# battery_monitor_6803-2_Rev3.net
KiCad netlist of a schematic drawn in EAGLE
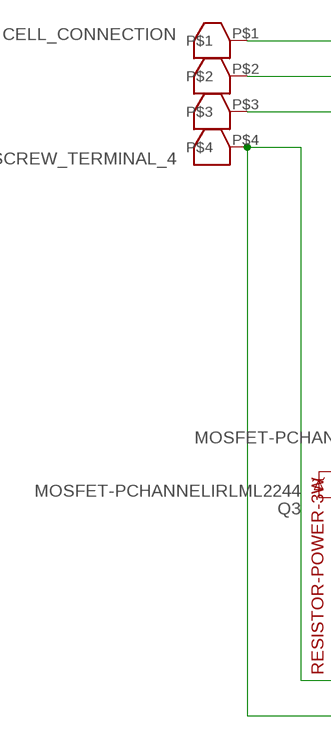
[diagram p0: schematic, sheet 1, part 1 of 2]
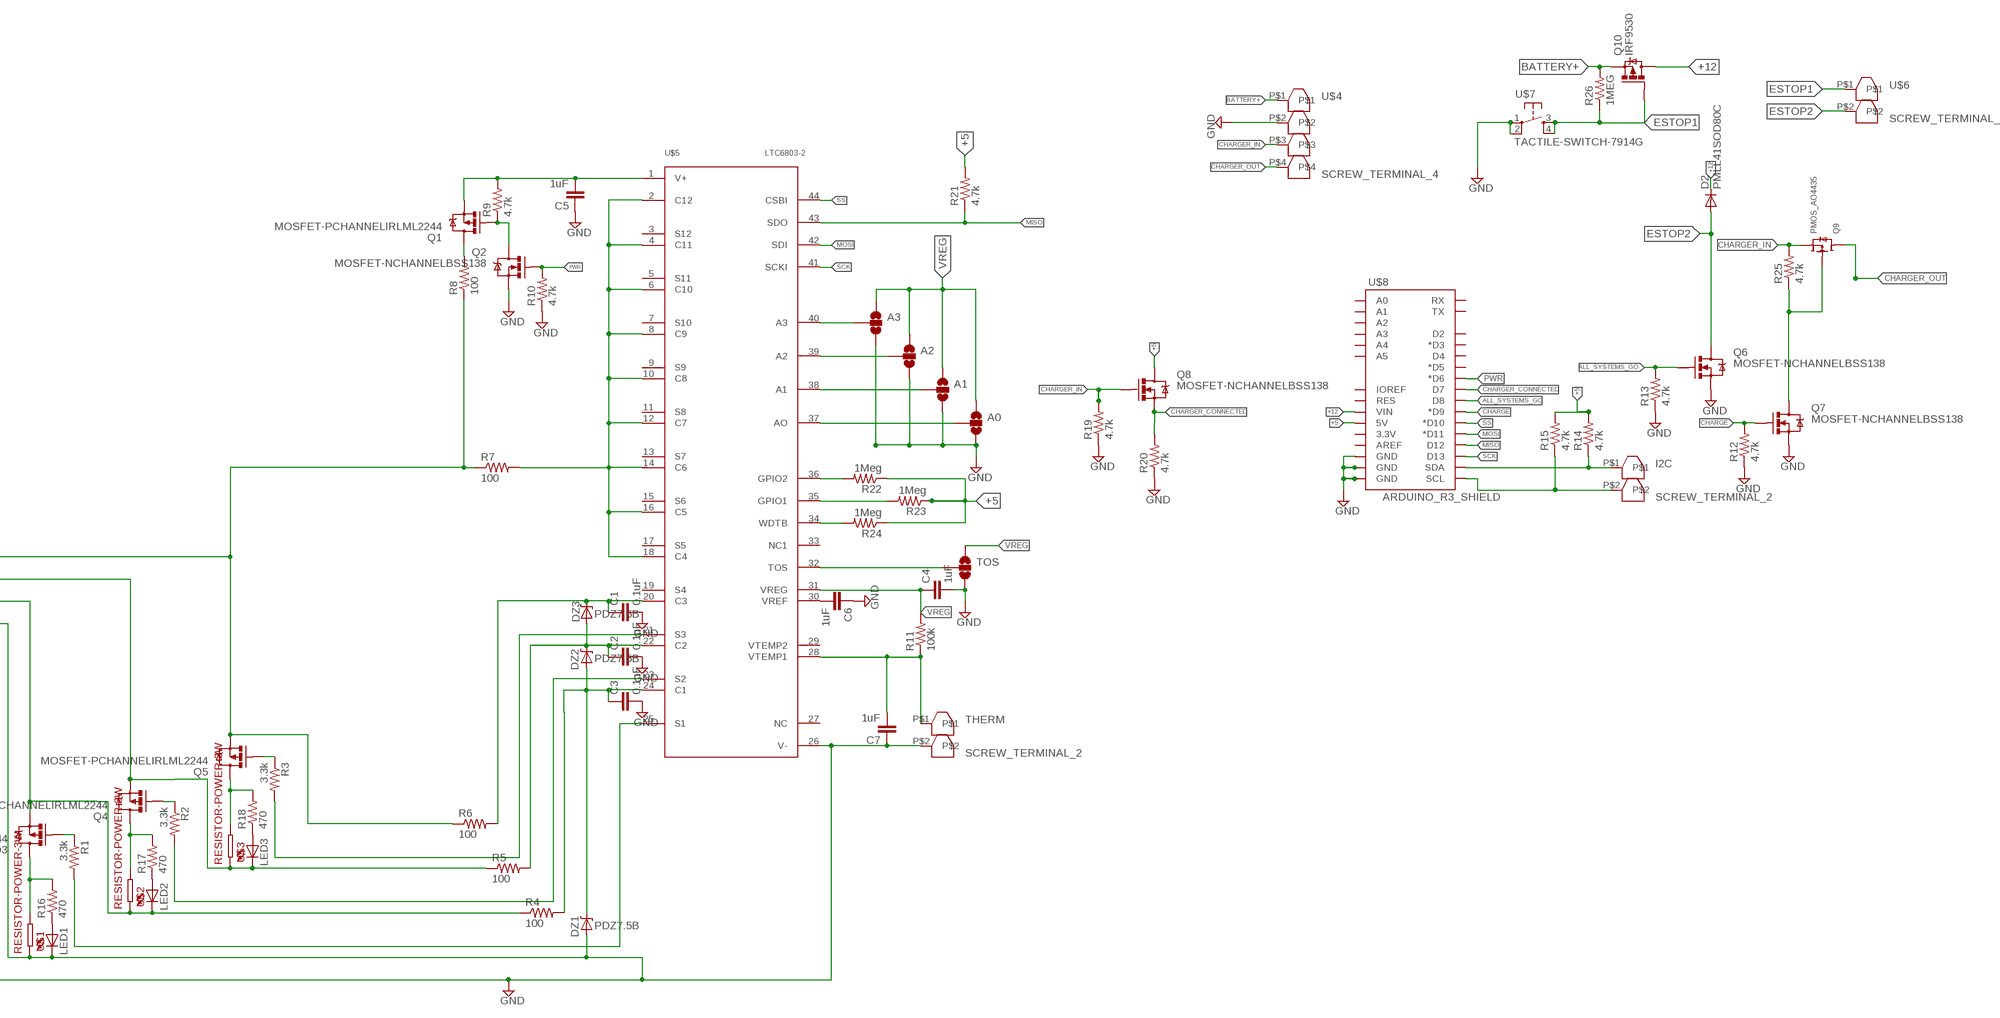
[diagram p1: schematic, sheet 1, part 2 of 2]

(export (version "E")
  (design (tool "Eeschema 10.0.6"))
  (components
    (comp (ref "A0")
      (value "SOLDERJUMPER_2WAYS")
      (footprint "eagle-import:SJ_3")
      (libsource (lib "eagle-import") (part "SOLDERJUMPER_2WAYS"))
    )
    (comp (ref "A1")
      (value "SOLDERJUMPER_2WAYS")
      (footprint "eagle-import:SJ_3")
      (libsource (lib "eagle-import") (part "SOLDERJUMPER_2WAYS"))
    )
    (comp (ref "A2")
      (value "SOLDERJUMPER_2WAYS")
      (footprint "eagle-import:SJ_3")
      (libsource (lib "eagle-import") (part "SOLDERJUMPER_2WAYS"))
    )
    (comp (ref "A3")
      (value "SOLDERJUMPER_2WAYS")
      (footprint "eagle-import:SJ_3")
      (libsource (lib "eagle-import") (part "SOLDERJUMPER_2WAYS"))
    )
    (comp (ref "C1")
      (value "0.1uF")
      (footprint "eagle-import:0603-CAP")
      (fields (field (name "MF") "AVX CORPORATION") (field (name "MPN") "0603YG104ZAT2A"))
      (libsource (lib "eagle-import") (part "0.1UF-100V-10%(0603)"))
    )
    (comp (ref "C2")
      (value "0.1uF")
      (footprint "eagle-import:0603-CAP")
      (fields (field (name "MF") "AVX CORPORATION") (field (name "MPN") "0603YG104ZAT2A"))
      (libsource (lib "eagle-import") (part "0.1UF-100V-10%(0603)"))
    )
    (comp (ref "C3")
      (value "0.1uF")
      (footprint "eagle-import:0603-CAP")
      (fields (field (name "MF") "AVX CORPORATION") (field (name "MPN") "0603YG104ZAT2A"))
      (libsource (lib "eagle-import") (part "0.1UF-100V-10%(0603)"))
    )
    (comp (ref "C4")
      (value "1uF")
      (footprint "eagle-import:0603-CAP")
      (fields (field (name "MPN") "C0603X5R0J105M030BC") (field (name "PROD_ID") "CAP-08390"))
      (libsource (lib "eagle-import") (part "0.1UF-100V-10%(0603)"))
    )
    (comp (ref "C5")
      (value "1uF")
      (footprint "eagle-import:0603-CAP")
      (fields (field (name "MPN") "C0603X5R0J105M030BC") (field (name "PROD_ID") "CAP-08390"))
      (libsource (lib "eagle-import") (part "0.1UF-100V-10%(0603)"))
    )
    (comp (ref "C6")
      (value "1uF")
      (footprint "eagle-import:0603-CAP")
      (fields (field (name "MPN") "C0603X5R0J105M030BC") (field (name "PROD_ID") "CAP-08390"))
      (libsource (lib "eagle-import") (part "0.1UF-100V-10%(0603)"))
    )
    (comp (ref "C7")
      (value "1uF")
      (footprint "eagle-import:0603-CAP")
      (fields (field (name "MPN") "C0603X5R0J105M030BC") (field (name "PROD_ID") "CAP-08390"))
      (libsource (lib "eagle-import") (part "0.1UF-100V-10%(0603)"))
    )
    (comp (ref "CELL_CONNECTION")
      (value "SCREW_TERMINAL_4")
      (footprint "eagle-import:SCREW_TERMINAL_4")
      (fields (field (name "MF") "TYCO ELECTRONICS") (field (name "MPN") "282834-4"))
      (libsource (lib "eagle-import") (part "SCREW_TERMINAL_4"))
    )
    (comp (ref "D2")
      (value "PMLL41SOD80C")
      (footprint "eagle-import:SOD80C")
      (fields (field (name "MF") "FAIRCHILD SEMICONDUCTOR") (field (name "MPN") "FDLL4148"))
      (libsource (lib "eagle-import") (part "PMLL41SOD80C"))
    )
    (comp (ref "DZ1")
      (value "PDZ7.5B")
      (footprint "eagle-import:SOD-323")
      (fields (field (name "MPN") "PDZ7.5B,115"))
      (libsource (lib "eagle-import") (part "DIODE-ZENER-BZT52"))
    )
    (comp (ref "DZ2")
      (value "PDZ7.5B")
      (footprint "eagle-import:SOD-323")
      (fields (field (name "MPN") "PDZ7.5B,115"))
      (libsource (lib "eagle-import") (part "DIODE-ZENER-BZT52"))
    )
    (comp (ref "DZ3")
      (value "PDZ7.5B")
      (footprint "eagle-import:SOD-323")
      (fields (field (name "MPN") "PDZ7.5B,115"))
      (libsource (lib "eagle-import") (part "DIODE-ZENER-BZT52"))
    )
    (comp (ref "I2C")
      (value "SCREW_TERMINAL_2")
      (footprint "eagle-import:SCREW_TERMINAL_2")
      (fields (field (name "MF") "TYCO ELECTRONICS") (field (name "MPN") "282834-2"))
      (libsource (lib "eagle-import") (part "isaac1_SCREW_TERMINAL_2"))
    )
    (comp (ref "LED1")
      (value "LED0603")
      (footprint "eagle-import:LED-0603")
      (fields (field (name "MPN") "150060RS75000"))
      (libsource (lib "eagle-import") (part "LED0603"))
    )
    (comp (ref "LED2")
      (value "LED0603")
      (footprint "eagle-import:LED-0603")
      (fields (field (name "MPN") "150060RS75000"))
      (libsource (lib "eagle-import") (part "LED0603"))
    )
    (comp (ref "LED3")
      (value "LED0603")
      (footprint "eagle-import:LED-0603")
      (fields (field (name "MPN") "150060RS75000"))
      (libsource (lib "eagle-import") (part "LED0603"))
    )
    (comp (ref "Q1")
      (value "MOSFET-PCHANNELIRLML2244")
      (footprint "eagle-import:SOT23-3")
      (fields (field (name "MPN") "SI2369DS-T1-GE3"))
      (libsource (lib "eagle-import") (part "MOSFET-PCHANNELIRLML2244"))
    )
    (comp (ref "Q2")
      (value "MOSFET-NCHANNELBSS138")
      (footprint "eagle-import:SOT23")
      (fields (field (name "MPN") "IRLML0030TRPBF"))
      (libsource (lib "eagle-import") (part "MOSFET-NCHANNELBSS138"))
    )
    (comp (ref "Q3")
      (value "MOSFET-PCHANNELIRLML2244")
      (footprint "eagle-import:SOT23-3")
      (fields (field (name "MPN") "SI2369DS-T1-GE3"))
      (libsource (lib "eagle-import") (part "MOSFET-PCHANNELIRLML2244"))
    )
    (comp (ref "Q4")
      (value "MOSFET-PCHANNELIRLML2244")
      (footprint "eagle-import:SOT23-3")
      (fields (field (name "MPN") "SI2369DS-T1-GE3"))
      (libsource (lib "eagle-import") (part "MOSFET-PCHANNELIRLML2244"))
    )
    (comp (ref "Q5")
      (value "MOSFET-PCHANNELIRLML2244")
      (footprint "eagle-import:SOT23-3")
      (fields (field (name "MPN") "SI2369DS-T1-GE3"))
      (libsource (lib "eagle-import") (part "MOSFET-PCHANNELIRLML2244"))
    )
    (comp (ref "Q6")
      (value "MOSFET-NCHANNELBSS138")
      (footprint "eagle-import:SOT23")
      (fields (field (name "MPN") "IRLML0030TRPBF"))
      (libsource (lib "eagle-import") (part "MOSFET-NCHANNELBSS138"))
    )
    (comp (ref "Q7")
      (value "MOSFET-NCHANNELBSS138")
      (footprint "eagle-import:SOT23")
      (fields (field (name "MPN") "IRLML0030TRPBF"))
      (libsource (lib "eagle-import") (part "MOSFET-NCHANNELBSS138"))
    )
    (comp (ref "Q8")
      (value "MOSFET-NCHANNELBSS138")
      (footprint "eagle-import:SOT23")
      (fields (field (name "MPN") "IRLML0030TRPBF") (field (name "PROD_ID") "TRANS-00830"))
      (libsource (lib "eagle-import") (part "MOSFET-NCHANNELBSS138"))
    )
    (comp (ref "Q9")
      (value "PMOS_AO4435")
      (footprint "eagle-import:SOIC8")
      (fields (field (name "MPN") "SI9407BDY-T1-GE3"))
      (libsource (lib "eagle-import") (part "PMOS_AO4435"))
    )
    (comp (ref "Q10")
      (value "IRF9530")
      (footprint "eagle-import:TO220BV")
      (fields (field (name "MPN") "NTE2383"))
      (libsource (lib "eagle-import") (part "IRF9530"))
    )
    (comp (ref "R1")
      (value "3.3k")
      (footprint "eagle-import:0603-RES")
      (fields (field (name "MF") "VISHAY/DALE") (field (name "MPN") "CRCW06033K00FKEA"))
      (libsource (lib "eagle-import") (part "3.3KOHM1/10W1%(0603)"))
    )
    (comp (ref "R2")
      (value "3.3k")
      (footprint "eagle-import:0603-RES")
      (fields (field (name "MF") "VISHAY/DALE") (field (name "MPN") "CRCW06033K00FKEA"))
      (libsource (lib "eagle-import") (part "3.3KOHM1/10W1%(0603)"))
    )
    (comp (ref "R3")
      (value "3.3k")
      (footprint "eagle-import:0603-RES")
      (fields (field (name "MF") "VISHAY/DALE") (field (name "MPN") "CRCW06033K00FKEA"))
      (libsource (lib "eagle-import") (part "3.3KOHM1/10W1%(0603)"))
    )
    (comp (ref "R4")
      (value "100")
      (footprint "eagle-import:0603-RES")
      (fields (field (name "MPN") "ERJ-1GNF1000C"))
      (libsource (lib "eagle-import") (part "3.3KOHM1/10W1%(0603)"))
    )
    (comp (ref "R5")
      (value "100")
      (footprint "eagle-import:0603-RES")
      (fields (field (name "MPN") "ERJ-1GNF1000C"))
      (libsource (lib "eagle-import") (part "3.3KOHM1/10W1%(0603)"))
    )
    (comp (ref "R6")
      (value "100")
      (footprint "eagle-import:0603-RES")
      (fields (field (name "MPN") "ERJ-1GNF1000C"))
      (libsource (lib "eagle-import") (part "3.3KOHM1/10W1%(0603)"))
    )
    (comp (ref "R7")
      (value "100")
      (footprint "eagle-import:0603-RES")
      (fields (field (name "MPN") "ERJ-1GNF1000C"))
      (libsource (lib "eagle-import") (part "3.3KOHM1/10W1%(0603)"))
    )
    (comp (ref "R8")
      (value "100")
      (footprint "eagle-import:0603-RES")
      (fields (field (name "MPN") "ERJ-1GNF1000C"))
      (libsource (lib "eagle-import") (part "3.3KOHM1/10W1%(0603)"))
    )
    (comp (ref "R9")
      (value "4.7k")
      (footprint "eagle-import:0603-RES")
      (fields (field (name "MF") "VISHAY/DALE") (field (name "MPN") "CRCW06034K70FKEA"))
      (libsource (lib "eagle-import") (part "3.3KOHM1/10W1%(0603)"))
    )
    (comp (ref "R10")
      (value "4.7k")
      (footprint "eagle-import:0603-RES")
      (fields (field (name "MF") "VISHAY/DALE") (field (name "MPN") "CRCW06034K70FKEA"))
      (libsource (lib "eagle-import") (part "3.3KOHM1/10W1%(0603)"))
    )
    (comp (ref "R11")
      (value "100k")
      (footprint "eagle-import:0603-RES")
      (fields (field (name "MF") "FARNELL") (field (name "MPN") "MC0063W06035100K"))
      (libsource (lib "eagle-import") (part "3.3KOHM1/10W1%(0603)"))
    )
    (comp (ref "R12")
      (value "4.7k")
      (footprint "eagle-import:0603-RES")
      (fields (field (name "MF") "VISHAY/DALE") (field (name "MPN") "CRCW06034K70FKEA"))
      (libsource (lib "eagle-import") (part "3.3KOHM1/10W1%(0603)"))
    )
    (comp (ref "R13")
      (value "4.7k")
      (footprint "eagle-import:0603-RES")
      (fields (field (name "MF") "VISHAY/DALE") (field (name "MPN") "CRCW06034K70FKEA"))
      (libsource (lib "eagle-import") (part "3.3KOHM1/10W1%(0603)"))
    )
    (comp (ref "R14")
      (value "4.7k")
      (footprint "eagle-import:0603-RES")
      (fields (field (name "MF") "VISHAY/DALE") (field (name "MPN") "CRCW06034K70FKEA"))
      (libsource (lib "eagle-import") (part "3.3KOHM1/10W1%(0603)"))
    )
    (comp (ref "R15")
      (value "4.7k")
      (footprint "eagle-import:0603-RES")
      (fields (field (name "MF") "VISHAY/DALE") (field (name "MPN") "CRCW06034K70FKEA"))
      (libsource (lib "eagle-import") (part "3.3KOHM1/10W1%(0603)"))
    )
    (comp (ref "R16")
      (value "470")
      (footprint "eagle-import:0603-RES")
      (fields (field (name "MPN") "ERJ-P03F4700V") (field (name "PROD_ID") "RES-07851"))
      (libsource (lib "eagle-import") (part "3.3KOHM1/10W1%(0603)"))
    )
    (comp (ref "R17")
      (value "470")
      (footprint "eagle-import:0603-RES")
      (fields (field (name "MPN") "ERJ-P03F4700V") (field (name "PROD_ID") "RES-07851"))
      (libsource (lib "eagle-import") (part "3.3KOHM1/10W1%(0603)"))
    )
    (comp (ref "R18")
      (value "470")
      (footprint "eagle-import:0603-RES")
      (fields (field (name "MPN") "ERJ-P03F4700V") (field (name "PROD_ID") "RES-07851"))
      (libsource (lib "eagle-import") (part "3.3KOHM1/10W1%(0603)"))
    )
    (comp (ref "R19")
      (value "4.7k")
      (footprint "eagle-import:0603-RES")
      (fields
        (field (name "MF") "VISHAY/DALE")
        (field (name "MPN") "CRCW06034K70FKEA")
        (field (name "PROD_ID") "RES-07851")
      )
      (libsource (lib "eagle-import") (part "3.3KOHM1/10W1%(0603)"))
    )
    (comp (ref "R20")
      (value "4.7k")
      (footprint "eagle-import:0603-RES")
      (fields
        (field (name "MF") "VISHAY/DALE")
        (field (name "MPN") "CRCW06034K70FKEA")
        (field (name "PROD_ID") "RES-07851")
      )
      (libsource (lib "eagle-import") (part "3.3KOHM1/10W1%(0603)"))
    )
    (comp (ref "R21")
      (value "4.7k")
      (footprint "eagle-import:0603-RES")
      (fields
        (field (name "MF") "VISHAY/DALE")
        (field (name "MPN") "CRCW06034K70FKEA")
        (field (name "PROD_ID") "RES-07851")
      )
      (libsource (lib "eagle-import") (part "3.3KOHM1/10W1%(0603)"))
    )
    (comp (ref "R22")
      (value "1Meg")
      (footprint "eagle-import:0603-RES")
      (fields (field (name "MPN") "ERJ-3EKF1004V") (field (name "PROD_ID") "RES-07851"))
      (libsource (lib "eagle-import") (part "3.3KOHM1/10W1%(0603)"))
    )
    (comp (ref "R23")
      (value "1Meg")
      (footprint "eagle-import:0603-RES")
      (fields (field (name "MPN") "ERJ-3EKF1004V") (field (name "PROD_ID") "RES-07851"))
      (libsource (lib "eagle-import") (part "3.3KOHM1/10W1%(0603)"))
    )
    (comp (ref "R24")
      (value "1Meg")
      (footprint "eagle-import:0603-RES")
      (fields (field (name "MPN") "ERJ-3EKF1004V") (field (name "PROD_ID") "RES-07851"))
      (libsource (lib "eagle-import") (part "3.3KOHM1/10W1%(0603)"))
    )
    (comp (ref "R25")
      (value "4.7k")
      (footprint "eagle-import:0603-RES")
      (fields
        (field (name "MF") "VISHAY/DALE")
        (field (name "MPN") "CRCW06034K70FKEA")
        (field (name "PROD_ID") "RES-07851")
      )
      (libsource (lib "eagle-import") (part "3.3KOHM1/10W1%(0603)"))
    )
    (comp (ref "R26")
      (value "1MEG")
      (footprint "eagle-import:0603-RES")
      (fields (field (name "MPN") "ERJ-3EKF1004V"))
      (libsource (lib "eagle-import") (part "3.3KOHM1/10W1%(0603)"))
    )
    (comp (ref "THERM")
      (value "SCREW_TERMINAL_2")
      (footprint "eagle-import:SCREW_TERMINAL_2")
      (fields (field (name "MF") "TYCO ELECTRONICS") (field (name "MPN") "282834-2"))
      (libsource (lib "eagle-import") (part "isaac1_SCREW_TERMINAL_2"))
    )
    (comp (ref "TOS")
      (value "SOLDERJUMPER_2WAYS")
      (footprint "eagle-import:SJ_3")
      (libsource (lib "eagle-import") (part "SOLDERJUMPER_2WAYS"))
    )
    (comp (ref "U$1")
      (value "RESISTOR-POWER-3W")
      (footprint "eagle-import:RESISTOR-3W")
      (fields (field (name "MPN") "ERG-3SJ200"))
      (libsource (lib "eagle-import") (part "RESISTOR-POWER-3W"))
    )
    (comp (ref "U$2")
      (value "RESISTOR-POWER-3W")
      (footprint "eagle-import:RESISTOR-3W")
      (fields (field (name "MPN") "ERG-3SJ200"))
      (libsource (lib "eagle-import") (part "RESISTOR-POWER-3W"))
    )
    (comp (ref "U$3")
      (value "RESISTOR-POWER-3W")
      (footprint "eagle-import:RESISTOR-3W")
      (fields (field (name "MPN") "ERG-3SJ200"))
      (libsource (lib "eagle-import") (part "RESISTOR-POWER-3W"))
    )
    (comp (ref "U$4")
      (value "SCREW_TERMINAL_4")
      (footprint "eagle-import:SCREW_TERMINAL_4")
      (fields (field (name "MF") "TYCO ELECTRONICS") (field (name "MPN") "282834-4"))
      (libsource (lib "eagle-import") (part "SCREW_TERMINAL_4"))
    )
    (comp (ref "U$5")
      (value "LTC6803-2")
      (footprint "eagle-import:FSOP-44")
      (libsource (lib "eagle-import") (part "LTC6803-2"))
    )
    (comp (ref "U$6")
      (value "SCREW_TERMINAL_2")
      (footprint "eagle-import:SCREW_TERMINAL_2")
      (fields (field (name "MF") "TYCO ELECTRONICS") (field (name "MPN") "282834-2"))
      (libsource (lib "eagle-import") (part "SCREW_TERMINAL_2"))
    )
    (comp (ref "U$7")
      (value "TACTILE-SWITCH-7914G")
      (footprint "eagle-import:7914G")
      (fields (field (name "MF") "BOURNS, INC.") (field (name "MPN") "7914G-1-000E"))
      (libsource (lib "eagle-import") (part "TACTILE-SWITCH-7914G"))
    )
    (comp (ref "U$8")
      (value "ARDUINO_R3_SHIELD")
      (footprint "eagle-import:UNO_R3_SHIELD")
      (libsource (lib "eagle-import") (part "ARDUINO_R3_SHIELD"))
    )
  )
  (nets
    (net (code "1") (name "+5") (class "Default")
      (node (ref "Q8") (pin "3") (pinfunction "D_3") (pintype "passive"))
      (node (ref "R14") (pin "2") (pinfunction "2_2") (pintype "passive"))
      (node (ref "R15") (pin "2") (pinfunction "2_2") (pintype "passive"))
      (node (ref "R21") (pin "2") (pinfunction "2_2") (pintype "passive"))
      (node (ref "R22") (pin "1") (pinfunction "1_1") (pintype "passive"))
      (node (ref "R23") (pin "1") (pinfunction "1_1") (pintype "passive"))
      (node (ref "R24") (pin "1") (pinfunction "1_1") (pintype "passive"))
      (node (ref "U$8") (pin "5V") (pinfunction "5V_5V") (pintype "bidirectional"))
    )
    (net (code "2") (name "+12") (class "Default")
      (node (ref "D2") (pin "C") (pinfunction "C_C") (pintype "passive"))
      (node (ref "Q10") (pin "D") (pinfunction "D_D") (pintype "passive"))
      (node (ref "U$8") (pin "VIN") (pinfunction "VIN_VIN") (pintype "bidirectional"))
    )
    (net (code "3") (name "ALL_SYSTEMS_GO") (class "Default")
      (node (ref "Q6") (pin "1") (pinfunction "G_1") (pintype "passive"))
      (node (ref "R13") (pin "2") (pinfunction "2_2") (pintype "passive"))
      (node (ref "U$8") (pin "D8") (pinfunction "D8_D8") (pintype "bidirectional"))
    )
    (net (code "4") (name "BATTERY+") (class "Default")
      (node (ref "Q10") (pin "S") (pinfunction "S_S") (pintype "passive"))
      (node (ref "R26") (pin "2") (pinfunction "2_2") (pintype "passive"))
      (node (ref "U$4") (pin "P$1") (pinfunction "P$1_P$1") (pintype "bidirectional"))
    )
    (net (code "5") (name "CHARGE") (class "Default")
      (node (ref "Q7") (pin "1") (pinfunction "G_1") (pintype "passive"))
      (node (ref "R12") (pin "2") (pinfunction "2_2") (pintype "passive"))
      (node (ref "U$8") (pin "D9") (pinfunction "*D9_D9") (pintype "bidirectional"))
    )
    (net (code "6") (name "CHARGER_CONNECTED") (class "Default")
      (node (ref "Q8") (pin "2") (pinfunction "S_2") (pintype "passive"))
      (node (ref "R20") (pin "2") (pinfunction "2_2") (pintype "passive"))
      (node (ref "U$8") (pin "D7") (pinfunction "D7_D7") (pintype "bidirectional"))
    )
    (net (code "7") (name "CHARGER_IN") (class "Default")
      (node (ref "Q8") (pin "1") (pinfunction "G_1") (pintype "passive"))
      (node (ref "Q9") (pin "1") (pinfunction "SOURCE_1") (pintype "bidirectional"))
      (node (ref "Q9") (pin "2") (pinfunction "SOURCE_2") (pintype "bidirectional"))
      (node (ref "Q9") (pin "3") (pinfunction "SOURCE_3") (pintype "bidirectional"))
      (node (ref "R19") (pin "2") (pinfunction "2_2") (pintype "passive"))
      (node (ref "R25") (pin "2") (pinfunction "2_2") (pintype "passive"))
      (node (ref "U$4") (pin "P$3") (pinfunction "P$3_P$3") (pintype "bidirectional"))
    )
    (net (code "8") (name "CHARGER_OUT") (class "Default")
      (node (ref "Q9") (pin "5") (pinfunction "DRAIN_5") (pintype "bidirectional"))
      (node (ref "Q9") (pin "6") (pinfunction "DRAIN_6") (pintype "bidirectional"))
      (node (ref "Q9") (pin "7") (pinfunction "DRAIN_7") (pintype "bidirectional"))
      (node (ref "Q9") (pin "8") (pinfunction "DRAIN_8") (pintype "bidirectional"))
      (node (ref "U$4") (pin "P$4") (pinfunction "P$4_P$4") (pintype "bidirectional"))
    )
    (net (code "9") (name "ESTOP1") (class "Default")
      (node (ref "Q10") (pin "G") (pinfunction "G_G") (pintype "passive"))
      (node (ref "R26") (pin "1") (pinfunction "1_1") (pintype "passive"))
      (node (ref "U$6") (pin "P$1") (pinfunction "P$1_P$1") (pintype "bidirectional"))
      (node (ref "U$7") (pin "3") (pinfunction "3_3") (pintype "passive"))
      (node (ref "U$7") (pin "4") (pinfunction "4_4") (pintype "passive"))
    )
    (net (code "10") (name "ESTOP2") (class "Default")
      (node (ref "D2") (pin "A") (pinfunction "A_A") (pintype "passive"))
      (node (ref "Q6") (pin "3") (pinfunction "D_3") (pintype "passive"))
      (node (ref "U$6") (pin "P$2") (pinfunction "P$2_P$2") (pintype "bidirectional"))
    )
    (net (code "11") (name "GND") (class "Default")
      (node (ref "A0") (pin "3") (pinfunction "3_3") (pintype "passive"))
      (node (ref "A1") (pin "3") (pinfunction "3_3") (pintype "passive"))
      (node (ref "A2") (pin "3") (pinfunction "3_3") (pintype "passive"))
      (node (ref "A3") (pin "3") (pinfunction "3_3") (pintype "passive"))
      (node (ref "C1") (pin "2") (pinfunction "2_2") (pintype "passive"))
      (node (ref "C2") (pin "2") (pinfunction "2_2") (pintype "passive"))
      (node (ref "C3") (pin "2") (pinfunction "2_2") (pintype "passive"))
      (node (ref "C4") (pin "2") (pinfunction "2_2") (pintype "passive"))
      (node (ref "C5") (pin "1") (pinfunction "1_1") (pintype "passive"))
      (node (ref "C6") (pin "1") (pinfunction "1_1") (pintype "passive"))
      (node (ref "C7") (pin "1") (pinfunction "1_1") (pintype "passive"))
      (node (ref "CELL_CONNECTION") (pin "P$4") (pinfunction "P$4_P$4") (pintype "bidirectional"))
      (node (ref "DZ1") (pin "2") (pinfunction "A_2") (pintype "passive"))
      (node (ref "LED1") (pin "C") (pinfunction "C_C") (pintype "passive"))
      (node (ref "Q2") (pin "2") (pinfunction "S_2") (pintype "passive"))
      (node (ref "Q6") (pin "2") (pinfunction "S_2") (pintype "passive"))
      (node (ref "Q7") (pin "2") (pinfunction "S_2") (pintype "passive"))
      (node (ref "R10") (pin "1") (pinfunction "1_1") (pintype "passive"))
      (node (ref "R12") (pin "1") (pinfunction "1_1") (pintype "passive"))
      (node (ref "R13") (pin "1") (pinfunction "1_1") (pintype "passive"))
      (node (ref "R19") (pin "1") (pinfunction "1_1") (pintype "passive"))
      (node (ref "R20") (pin "1") (pinfunction "1_1") (pintype "passive"))
      (node (ref "THERM") (pin "P$2") (pinfunction "P$2_P$2") (pintype "bidirectional"))
      (node (ref "TOS") (pin "3") (pinfunction "3_3") (pintype "passive"))
      (node (ref "U$1") (pin "P$2") (pinfunction "P$2_P$2") (pintype "bidirectional"))
      (node (ref "U$4") (pin "P$2") (pinfunction "P$2_P$2") (pintype "bidirectional"))
      (node (ref "U$5") (pin "26") (pinfunction "V-_26") (pintype "bidirectional"))
      (node (ref "U$7") (pin "1") (pinfunction "1_1") (pintype "passive"))
      (node (ref "U$7") (pin "2") (pinfunction "2_2") (pintype "passive"))
      (node (ref "U$8") (pin "GND@0") (pinfunction "GND_GND@0") (pintype "bidirectional"))
      (node (ref "U$8") (pin "GND@1") (pinfunction "GND_GND@1") (pintype "bidirectional"))
      (node (ref "U$8") (pin "GND@2") (pinfunction "GND_GND@2") (pintype "bidirectional"))
    )
    (net (code "12") (name "MISO") (class "Default")
      (node (ref "R21") (pin "1") (pinfunction "1_1") (pintype "passive"))
      (node (ref "U$5") (pin "43") (pinfunction "SDO_43") (pintype "bidirectional"))
      (node (ref "U$8") (pin "D12") (pinfunction "D12_D12") (pintype "bidirectional"))
    )
    (net (code "13") (name "MOSI") (class "Default")
      (node (ref "U$5") (pin "42") (pinfunction "SDI_42") (pintype "bidirectional"))
      (node (ref "U$8") (pin "D11") (pinfunction "*D11_D11") (pintype "bidirectional"))
    )
    (net (code "14") (name "Net-(DZ1-C)") (class "Default")
      (node (ref "C3") (pin "1") (pinfunction "1_1") (pintype "passive"))
      (node (ref "DZ1") (pin "1") (pinfunction "C_1") (pintype "passive"))
      (node (ref "DZ2") (pin "2") (pinfunction "A_2") (pintype "passive"))
      (node (ref "R4") (pin "2") (pinfunction "2_2") (pintype "passive"))
      (node (ref "U$5") (pin "24") (pinfunction "C1_24") (pintype "bidirectional"))
    )
    (net (code "15") (name "Net-(DZ2-C)") (class "Default")
      (node (ref "C2") (pin "1") (pinfunction "1_1") (pintype "passive"))
      (node (ref "DZ2") (pin "1") (pinfunction "C_1") (pintype "passive"))
      (node (ref "DZ3") (pin "2") (pinfunction "A_2") (pintype "passive"))
      (node (ref "R5") (pin "2") (pinfunction "2_2") (pintype "passive"))
      (node (ref "U$5") (pin "22") (pinfunction "C2_22") (pintype "bidirectional"))
    )
    (net (code "16") (name "Net-(DZ3-C)") (class "Default")
      (node (ref "C1") (pin "1") (pinfunction "1_1") (pintype "passive"))
      (node (ref "DZ3") (pin "1") (pinfunction "C_1") (pintype "passive"))
      (node (ref "R6") (pin "2") (pinfunction "2_2") (pintype "passive"))
      (node (ref "U$5") (pin "20") (pinfunction "C3_20") (pintype "bidirectional"))
    )
    (net (code "17") (name "Net-(I2C-PadP$1)") (class "Default")
      (node (ref "I2C") (pin "P$1") (pinfunction "P$1_P$1") (pintype "bidirectional"))
      (node (ref "R14") (pin "1") (pinfunction "1_1") (pintype "passive"))
      (node (ref "U$8") (pin "SDA") (pinfunction "SDA_SDA") (pintype "bidirectional"))
    )
    (net (code "18") (name "Net-(I2C-PadP$2)") (class "Default")
      (node (ref "I2C") (pin "P$2") (pinfunction "P$2_P$2") (pintype "bidirectional"))
      (node (ref "R15") (pin "1") (pinfunction "1_1") (pintype "passive"))
      (node (ref "U$8") (pin "SCL") (pinfunction "SCL_SCL") (pintype "bidirectional"))
    )
    (net (code "19") (name "Net-(LED1-PadA)") (class "Default")
      (node (ref "LED1") (pin "A") (pinfunction "A_A") (pintype "passive"))
      (node (ref "R16") (pin "1") (pinfunction "1_1") (pintype "passive"))
    )
    (net (code "20") (name "Net-(LED2-PadA)") (class "Default")
      (node (ref "LED2") (pin "A") (pinfunction "A_A") (pintype "passive"))
      (node (ref "R17") (pin "1") (pinfunction "1_1") (pintype "passive"))
    )
    (net (code "21") (name "Net-(LED3-PadA)") (class "Default")
      (node (ref "LED3") (pin "A") (pinfunction "A_A") (pintype "passive"))
      (node (ref "R18") (pin "1") (pinfunction "1_1") (pintype "passive"))
    )
    (net (code "22") (name "Net-(Q1-D)") (class "Default")
      (node (ref "Q1") (pin "3") (pinfunction "D_3") (pintype "passive"))
      (node (ref "R8") (pin "2") (pinfunction "2_2") (pintype "passive"))
    )
    (net (code "23") (name "Net-(Q1-G)") (class "Default")
      (node (ref "Q1") (pin "1") (pinfunction "G_1") (pintype "passive"))
      (node (ref "Q2") (pin "3") (pinfunction "D_3") (pintype "passive"))
      (node (ref "R9") (pin "1") (pinfunction "1_1") (pintype "passive"))
    )
    (net (code "24") (name "Net-(Q1-S)") (class "Default")
      (node (ref "C5") (pin "2") (pinfunction "2_2") (pintype "passive"))
      (node (ref "Q1") (pin "2") (pinfunction "S_2") (pintype "passive"))
      (node (ref "R9") (pin "2") (pinfunction "2_2") (pintype "passive"))
      (node (ref "U$5") (pin "1") (pinfunction "V+_1") (pintype "bidirectional"))
    )
    (net (code "25") (name "Net-(Q3-D)") (class "Default")
      (node (ref "Q3") (pin "3") (pinfunction "D_3") (pintype "passive"))
      (node (ref "R16") (pin "2") (pinfunction "2_2") (pintype "passive"))
      (node (ref "U$1") (pin "P$1") (pinfunction "P$1_P$1") (pintype "bidirectional"))
    )
    (net (code "26") (name "Net-(Q3-G)") (class "Default")
      (node (ref "Q3") (pin "1") (pinfunction "G_1") (pintype "passive"))
      (node (ref "R1") (pin "1") (pinfunction "1_1") (pintype "passive"))
    )
    (net (code "27") (name "Net-(Q3-S)") (class "Default")
      (node (ref "CELL_CONNECTION") (pin "P$3") (pinfunction "P$3_P$3") (pintype "bidirectional"))
      (node (ref "LED2") (pin "C") (pinfunction "C_C") (pintype "passive"))
      (node (ref "Q3") (pin "2") (pinfunction "S_2") (pintype "passive"))
      (node (ref "R4") (pin "1") (pinfunction "1_1") (pintype "passive"))
      (node (ref "U$2") (pin "P$2") (pinfunction "P$2_P$2") (pintype "bidirectional"))
    )
    (net (code "28") (name "Net-(Q4-D)") (class "Default")
      (node (ref "Q4") (pin "3") (pinfunction "D_3") (pintype "passive"))
      (node (ref "R17") (pin "2") (pinfunction "2_2") (pintype "passive"))
      (node (ref "U$2") (pin "P$1") (pinfunction "P$1_P$1") (pintype "bidirectional"))
    )
    (net (code "29") (name "Net-(Q4-G)") (class "Default")
      (node (ref "Q4") (pin "1") (pinfunction "G_1") (pintype "passive"))
      (node (ref "R2") (pin "1") (pinfunction "1_1") (pintype "passive"))
    )
    (net (code "30") (name "Net-(Q4-S)") (class "Default")
      (node (ref "CELL_CONNECTION") (pin "P$2") (pinfunction "P$2_P$2") (pintype "bidirectional"))
      (node (ref "LED3") (pin "C") (pinfunction "C_C") (pintype "passive"))
      (node (ref "Q4") (pin "2") (pinfunction "S_2") (pintype "passive"))
      (node (ref "R5") (pin "1") (pinfunction "1_1") (pintype "passive"))
      (node (ref "U$3") (pin "P$2") (pinfunction "P$2_P$2") (pintype "bidirectional"))
    )
    (net (code "31") (name "Net-(Q5-D)") (class "Default")
      (node (ref "Q5") (pin "3") (pinfunction "D_3") (pintype "passive"))
      (node (ref "R18") (pin "2") (pinfunction "2_2") (pintype "passive"))
      (node (ref "U$3") (pin "P$1") (pinfunction "P$1_P$1") (pintype "bidirectional"))
    )
    (net (code "32") (name "Net-(Q5-G)") (class "Default")
      (node (ref "Q5") (pin "1") (pinfunction "G_1") (pintype "passive"))
      (node (ref "R3") (pin "1") (pinfunction "1_1") (pintype "passive"))
    )
    (net (code "33") (name "Net-(Q5-S)") (class "Default")
      (node (ref "CELL_CONNECTION") (pin "P$1") (pinfunction "P$1_P$1") (pintype "bidirectional"))
      (node (ref "Q5") (pin "2") (pinfunction "S_2") (pintype "passive"))
      (node (ref "R6") (pin "1") (pinfunction "1_1") (pintype "passive"))
      (node (ref "R7") (pin "1") (pinfunction "1_1") (pintype "passive"))
      (node (ref "R8") (pin "1") (pinfunction "1_1") (pintype "passive"))
    )
    (net (code "34") (name "Net-(Q7-D)") (class "Default")
      (node (ref "Q7") (pin "3") (pinfunction "D_3") (pintype "passive"))
      (node (ref "Q9") (pin "4") (pinfunction "GATE_4") (pintype "bidirectional"))
      (node (ref "R25") (pin "1") (pinfunction "1_1") (pintype "passive"))
    )
    (net (code "35") (name "Net-(U$5-A1)") (class "Default")
      (node (ref "A1") (pin "2") (pinfunction "2_2") (pintype "passive"))
      (node (ref "U$5") (pin "38") (pinfunction "A1_38") (pintype "bidirectional"))
    )
    (net (code "36") (name "Net-(U$5-A2)") (class "Default")
      (node (ref "A2") (pin "2") (pinfunction "2_2") (pintype "passive"))
      (node (ref "U$5") (pin "39") (pinfunction "A2_39") (pintype "bidirectional"))
    )
    (net (code "37") (name "Net-(U$5-A3)") (class "Default")
      (node (ref "A3") (pin "2") (pinfunction "2_2") (pintype "passive"))
      (node (ref "U$5") (pin "40") (pinfunction "A3_40") (pintype "bidirectional"))
    )
    (net (code "38") (name "Net-(U$5-AO)") (class "Default")
      (node (ref "A0") (pin "2") (pinfunction "2_2") (pintype "passive"))
      (node (ref "U$5") (pin "37") (pinfunction "AO_37") (pintype "bidirectional"))
    )
    (net (code "39") (name "Net-(U$5-C10)") (class "Default")
      (node (ref "R7") (pin "2") (pinfunction "2_2") (pintype "passive"))
      (node (ref "U$5") (pin "10") (pinfunction "C8_10") (pintype "bidirectional"))
      (node (ref "U$5") (pin "12") (pinfunction "C7_12") (pintype "bidirectional"))
      (node (ref "U$5") (pin "14") (pinfunction "C6_14") (pintype "bidirectional"))
      (node (ref "U$5") (pin "16") (pinfunction "C5_16") (pintype "bidirectional"))
      (node (ref "U$5") (pin "18") (pinfunction "C4_18") (pintype "bidirectional"))
      (node (ref "U$5") (pin "2") (pinfunction "C12_2") (pintype "bidirectional"))
      (node (ref "U$5") (pin "4") (pinfunction "C11_4") (pintype "bidirectional"))
      (node (ref "U$5") (pin "6") (pinfunction "C10_6") (pintype "bidirectional"))
      (node (ref "U$5") (pin "8") (pinfunction "C9_8") (pintype "bidirectional"))
    )
    (net (code "40") (name "Net-(U$5-GPIO1)") (class "Default")
      (node (ref "R23") (pin "2") (pinfunction "2_2") (pintype "passive"))
      (node (ref "U$5") (pin "35") (pinfunction "GPIO1_35") (pintype "bidirectional"))
    )
    (net (code "41") (name "Net-(U$5-GPIO2)") (class "Default")
      (node (ref "R22") (pin "2") (pinfunction "2_2") (pintype "passive"))
      (node (ref "U$5") (pin "36") (pinfunction "GPIO2_36") (pintype "bidirectional"))
    )
    (net (code "42") (name "Net-(U$5-S1)") (class "Default")
      (node (ref "R1") (pin "2") (pinfunction "2_2") (pintype "passive"))
      (node (ref "U$5") (pin "25") (pinfunction "S1_25") (pintype "bidirectional"))
    )
    (net (code "43") (name "Net-(U$5-S2)") (class "Default")
      (node (ref "R2") (pin "2") (pinfunction "2_2") (pintype "passive"))
      (node (ref "U$5") (pin "23") (pinfunction "S2_23") (pintype "bidirectional"))
    )
    (net (code "44") (name "Net-(U$5-S3)") (class "Default")
      (node (ref "R3") (pin "2") (pinfunction "2_2") (pintype "passive"))
      (node (ref "U$5") (pin "21") (pinfunction "S3_21") (pintype "bidirectional"))
    )
    (net (code "45") (name "Net-(U$5-TOS)") (class "Default")
      (node (ref "TOS") (pin "2") (pinfunction "2_2") (pintype "passive"))
      (node (ref "U$5") (pin "32") (pinfunction "TOS_32") (pintype "bidirectional"))
    )
    (net (code "46") (name "Net-(U$5-VREF)") (class "Default")
      (node (ref "C6") (pin "2") (pinfunction "2_2") (pintype "passive"))
      (node (ref "U$5") (pin "30") (pinfunction "VREF_30") (pintype "bidirectional"))
    )
    (net (code "47") (name "Net-(U$5-VTEMP1)") (class "Default")
      (node (ref "C7") (pin "2") (pinfunction "2_2") (pintype "passive"))
      (node (ref "R11") (pin "1") (pinfunction "1_1") (pintype "passive"))
      (node (ref "THERM") (pin "P$1") (pinfunction "P$1_P$1") (pintype "bidirectional"))
      (node (ref "U$5") (pin "28") (pinfunction "VTEMP1_28") (pintype "bidirectional"))
    )
    (net (code "48") (name "Net-(U$5-WDTB)") (class "Default")
      (node (ref "R24") (pin "2") (pinfunction "2_2") (pintype "passive"))
      (node (ref "U$5") (pin "34") (pinfunction "WDTB_34") (pintype "bidirectional"))
    )
    (net (code "49") (name "PWR") (class "Default")
      (node (ref "Q2") (pin "1") (pinfunction "G_1") (pintype "passive"))
      (node (ref "R10") (pin "2") (pinfunction "2_2") (pintype "passive"))
      (node (ref "U$8") (pin "D6") (pinfunction "*D6_D6") (pintype "bidirectional"))
    )
    (net (code "50") (name "SCK") (class "Default")
      (node (ref "U$5") (pin "41") (pinfunction "SCKI_41") (pintype "bidirectional"))
      (node (ref "U$8") (pin "D13") (pinfunction "D13_D13") (pintype "bidirectional"))
    )
    (net (code "51") (name "SS") (class "Default")
      (node (ref "U$5") (pin "44") (pinfunction "CSBI_44") (pintype "bidirectional"))
      (node (ref "U$8") (pin "D10") (pinfunction "*D10_D10") (pintype "bidirectional"))
    )
    (net (code "52") (name "VREG") (class "Default")
      (node (ref "A0") (pin "1") (pinfunction "1_1") (pintype "passive"))
      (node (ref "A1") (pin "1") (pinfunction "1_1") (pintype "passive"))
      (node (ref "A2") (pin "1") (pinfunction "1_1") (pintype "passive"))
      (node (ref "A3") (pin "1") (pinfunction "1_1") (pintype "passive"))
      (node (ref "C4") (pin "1") (pinfunction "1_1") (pintype "passive"))
      (node (ref "R11") (pin "2") (pinfunction "2_2") (pintype "passive"))
      (node (ref "TOS") (pin "1") (pinfunction "1_1") (pintype "passive"))
      (node (ref "U$5") (pin "31") (pinfunction "VREG_31") (pintype "bidirectional"))
    )
    (net (code "53") (name "unconnected-(U$5-NC-Pad27)") (class "Default")
      (node (ref "U$5") (pin "27") (pinfunction "NC_27") (pintype "bidirectional"))
    )
    (net (code "54") (name "unconnected-(U$5-NC1-Pad33)") (class "Default")
      (node (ref "U$5") (pin "33") (pinfunction "NC1_33") (pintype "bidirectional"))
    )
    (net (code "55") (name "unconnected-(U$5-S4-Pad19)") (class "Default")
      (node (ref "U$5") (pin "19") (pinfunction "S4_19") (pintype "bidirectional"))
    )
    (net (code "56") (name "unconnected-(U$5-S5-Pad17)") (class "Default")
      (node (ref "U$5") (pin "17") (pinfunction "S5_17") (pintype "bidirectional"))
    )
    (net (code "57") (name "unconnected-(U$5-S6-Pad15)") (class "Default")
      (node (ref "U$5") (pin "15") (pinfunction "S6_15") (pintype "bidirectional"))
    )
    (net (code "58") (name "unconnected-(U$5-S7-Pad13)") (class "Default")
      (node (ref "U$5") (pin "13") (pinfunction "S7_13") (pintype "bidirectional"))
    )
    (net (code "59") (name "unconnected-(U$5-S8-Pad11)") (class "Default")
      (node (ref "U$5") (pin "11") (pinfunction "S8_11") (pintype "bidirectional"))
    )
    (net (code "60") (name "unconnected-(U$5-S9-Pad9)") (class "Default")
      (node (ref "U$5") (pin "9") (pinfunction "S9_9") (pintype "bidirectional"))
    )
    (net (code "61") (name "unconnected-(U$5-S10-Pad7)") (class "Default")
      (node (ref "U$5") (pin "7") (pinfunction "S10_7") (pintype "bidirectional"))
    )
    (net (code "62") (name "unconnected-(U$5-S11-Pad5)") (class "Default")
      (node (ref "U$5") (pin "5") (pinfunction "S11_5") (pintype "bidirectional"))
    )
    (net (code "63") (name "unconnected-(U$5-S12-Pad3)") (class "Default")
      (node (ref "U$5") (pin "3") (pinfunction "S12_3") (pintype "bidirectional"))
    )
    (net (code "64") (name "unconnected-(U$5-VTEMP2-Pad29)") (class "Default")
      (node (ref "U$5") (pin "29") (pinfunction "VTEMP2_29") (pintype "bidirectional"))
    )
    (net (code "65") (name "unconnected-(U$8-*D3-PadD3)") (class "Default")
      (node (ref "U$8") (pin "D3") (pinfunction "*D3_D3") (pintype "bidirectional"))
    )
    (net (code "66") (name "unconnected-(U$8-*D5-PadD5)") (class "Default")
      (node (ref "U$8") (pin "D5") (pinfunction "*D5_D5") (pintype "bidirectional"))
    )
    (net (code "67") (name "unconnected-(U$8-Pad3.3V)") (class "Default")
      (node (ref "U$8") (pin "3.3V") (pinfunction "3.3V_3.3V") (pintype "bidirectional"))
    )
    (net (code "68") (name "unconnected-(U$8-PadA0)") (class "Default")
      (node (ref "U$8") (pin "A0") (pinfunction "A0_A0") (pintype "bidirectional"))
    )
    (net (code "69") (name "unconnected-(U$8-PadA1)") (class "Default")
      (node (ref "U$8") (pin "A1") (pinfunction "A1_A1") (pintype "bidirectional"))
    )
    (net (code "70") (name "unconnected-(U$8-PadA2)") (class "Default")
      (node (ref "U$8") (pin "A2") (pinfunction "A2_A2") (pintype "bidirectional"))
    )
    (net (code "71") (name "unconnected-(U$8-PadA3)") (class "Default")
      (node (ref "U$8") (pin "A3") (pinfunction "A3_A3") (pintype "bidirectional"))
    )
    (net (code "72") (name "unconnected-(U$8-PadA4)") (class "Default")
      (node (ref "U$8") (pin "A4") (pinfunction "A4_A4") (pintype "bidirectional"))
    )
    (net (code "73") (name "unconnected-(U$8-PadA5)") (class "Default")
      (node (ref "U$8") (pin "A5") (pinfunction "A5_A5") (pintype "bidirectional"))
    )
    (net (code "74") (name "unconnected-(U$8-PadAREF)") (class "Default")
      (node (ref "U$8") (pin "AREF") (pinfunction "AREF_AREF") (pintype "bidirectional"))
    )
    (net (code "75") (name "unconnected-(U$8-PadD2)") (class "Default")
      (node (ref "U$8") (pin "D2") (pinfunction "D2_D2") (pintype "bidirectional"))
    )
    (net (code "76") (name "unconnected-(U$8-PadD4)") (class "Default")
      (node (ref "U$8") (pin "D4") (pinfunction "D4_D4") (pintype "bidirectional"))
    )
    (net (code "77") (name "unconnected-(U$8-PadIOREF)") (class "Default")
      (node (ref "U$8") (pin "IOREF") (pinfunction "IOREF_IOREF") (pintype "bidirectional"))
    )
    (net (code "78") (name "unconnected-(U$8-PadRES)") (class "Default")
      (node (ref "U$8") (pin "RES") (pinfunction "RES_RES") (pintype "bidirectional"))
    )
    (net (code "79") (name "unconnected-(U$8-PadRX)") (class "Default")
      (node (ref "U$8") (pin "RX") (pinfunction "RX_RX") (pintype "bidirectional"))
    )
    (net (code "80") (name "unconnected-(U$8-PadTX)") (class "Default")
      (node (ref "U$8") (pin "TX") (pinfunction "TX_TX") (pintype "bidirectional"))
    )
  )
)
